# canSlaveV05_Abm.net
KiCad netlist of a schematic drawn in EAGLE
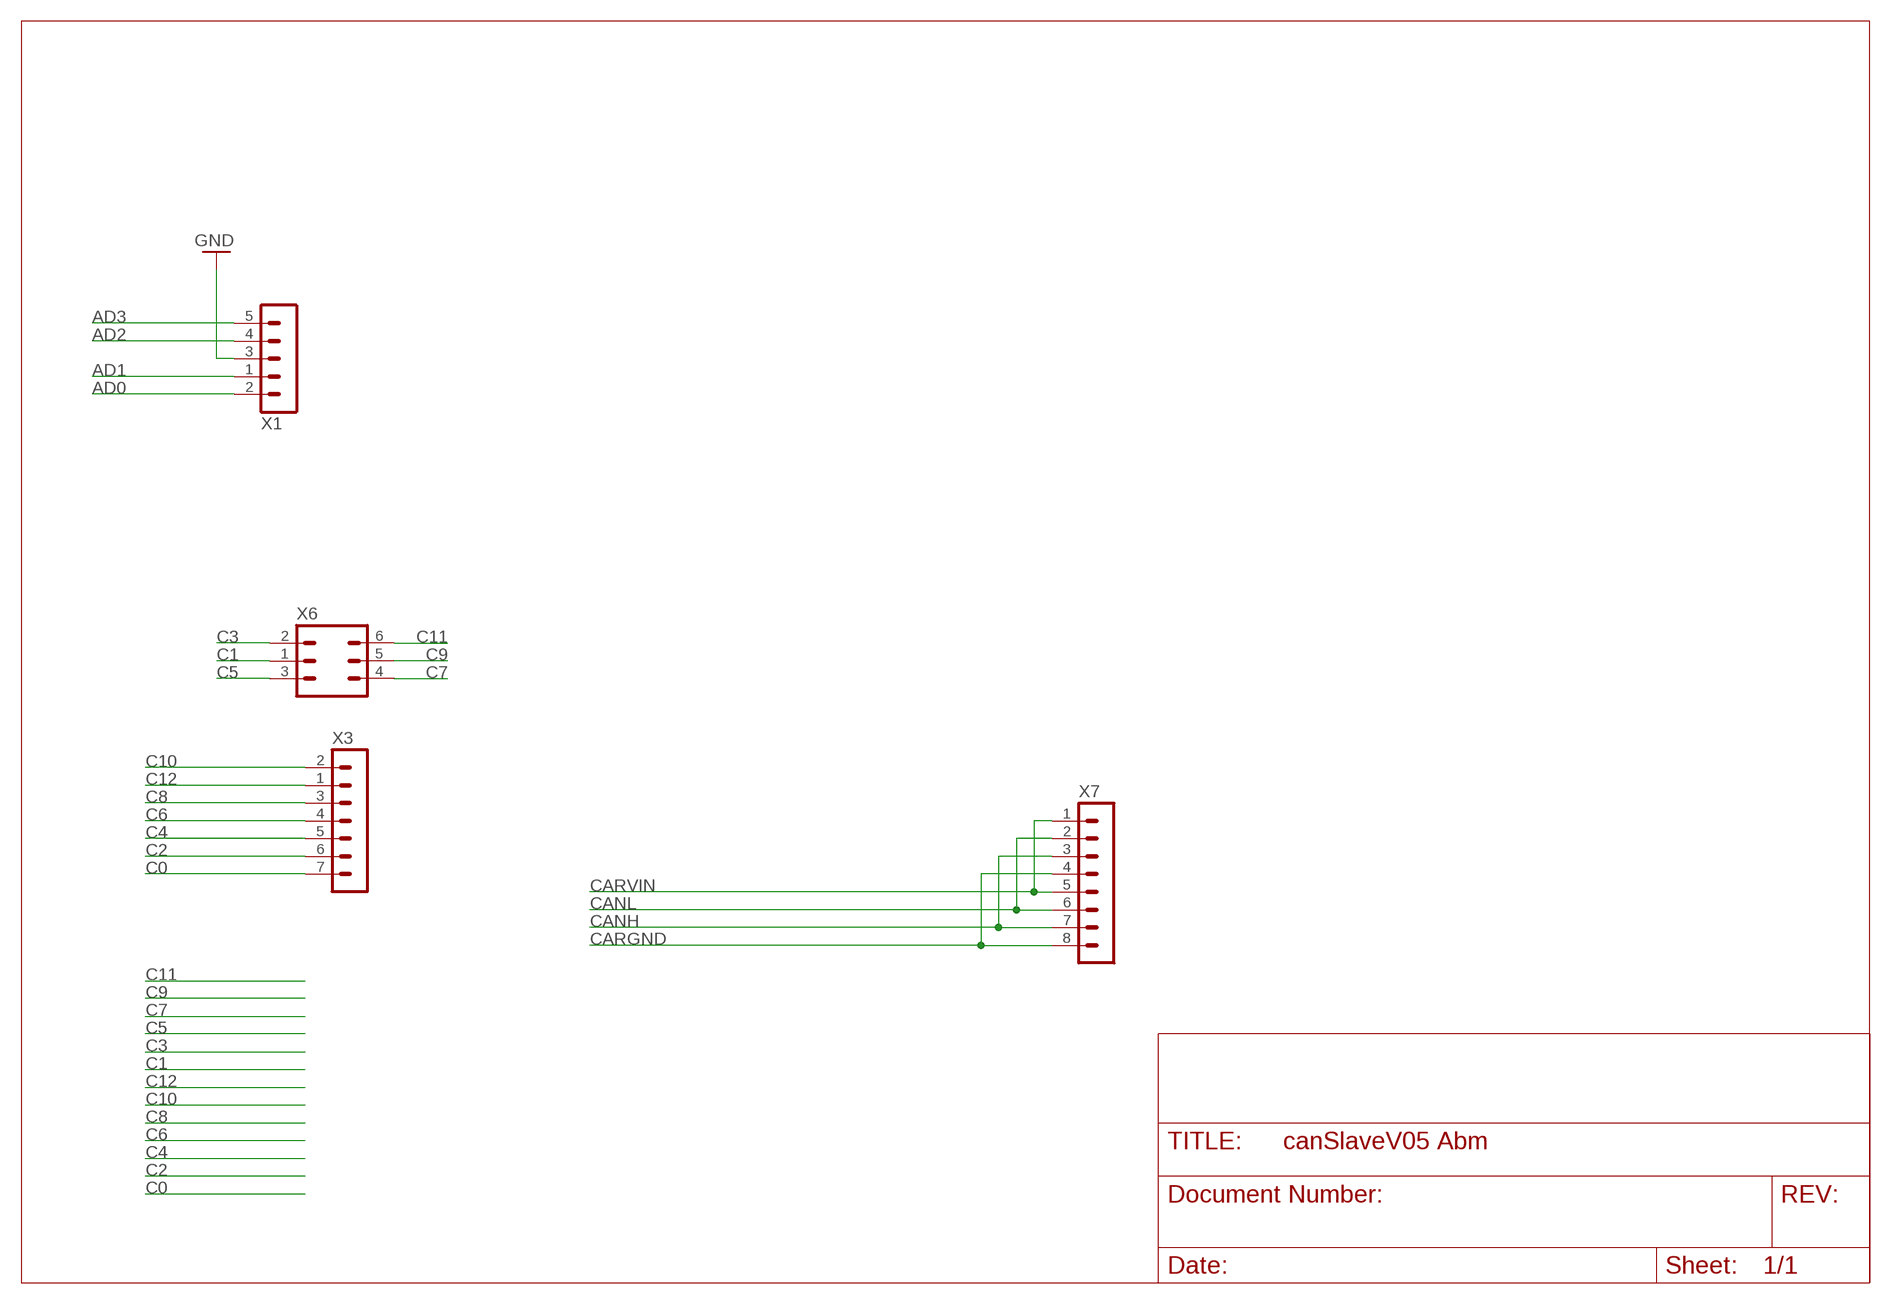
[diagram p0: schematic, sheet 1]

(export (version "E")
  (design (tool "Eeschema 10.0.6"))
  (components
    (comp (ref "X1")
      (value "HEADER_POS5_43650-0509")
      (footprint "eagle-import:43650-0509")
      (libsource (lib "eagle-import") (part "HEADER_POS5_?43650-0509"))
    )
    (comp (ref "X3")
      (value "HEADER_POS7_43650-0709")
      (footprint "eagle-import:43650-0709")
      (libsource (lib "eagle-import") (part "HEADER_POS7_?43650-0709"))
    )
    (comp (ref "X6")
      (value "HEADER_POS6_43650-0609")
      (footprint "eagle-import:43650-0609")
      (libsource (lib "eagle-import") (part "HEADER_POS6_?43650-0609"))
    )
    (comp (ref "X7")
      (value "HEADER_POS8_43045-0800")
      (footprint "eagle-import:43045-0800")
      (libsource (lib "eagle-import") (part "HEADER_POS8_?43045-0800"))
    )
  )
  (nets
    (net (code "1") (name "/AD0") (class "Default")
      (node (ref "X1") (pin "2") (pinfunction "1_2") (pintype "passive"))
    )
    (net (code "2") (name "/AD1") (class "Default")
      (node (ref "X1") (pin "1") (pinfunction "2_1") (pintype "passive"))
    )
    (net (code "3") (name "/AD2") (class "Default")
      (node (ref "X1") (pin "4") (pinfunction "4_4") (pintype "passive"))
    )
    (net (code "4") (name "/AD3") (class "Default")
      (node (ref "X1") (pin "5") (pinfunction "5_5") (pintype "passive"))
    )
    (net (code "5") (name "/C0") (class "Default")
      (node (ref "X3") (pin "7") (pinfunction "7_7") (pintype "passive"))
    )
    (net (code "6") (name "/C1") (class "Default")
      (node (ref "X6") (pin "1") (pinfunction "2_1") (pintype "passive"))
    )
    (net (code "7") (name "/C2") (class "Default")
      (node (ref "X3") (pin "6") (pinfunction "6_6") (pintype "passive"))
    )
    (net (code "8") (name "/C3") (class "Default")
      (node (ref "X6") (pin "2") (pinfunction "1_2") (pintype "passive"))
    )
    (net (code "9") (name "/C4") (class "Default")
      (node (ref "X3") (pin "5") (pinfunction "5_5") (pintype "passive"))
    )
    (net (code "10") (name "/C5") (class "Default")
      (node (ref "X6") (pin "3") (pinfunction "3_3") (pintype "passive"))
    )
    (net (code "11") (name "/C6") (class "Default")
      (node (ref "X3") (pin "4") (pinfunction "4_4") (pintype "passive"))
    )
    (net (code "12") (name "/C7") (class "Default")
      (node (ref "X6") (pin "4") (pinfunction "4_4") (pintype "passive"))
    )
    (net (code "13") (name "/C8") (class "Default")
      (node (ref "X3") (pin "3") (pinfunction "3_3") (pintype "passive"))
    )
    (net (code "14") (name "/C9") (class "Default")
      (node (ref "X6") (pin "5") (pinfunction "5_5") (pintype "passive"))
    )
    (net (code "15") (name "/C10") (class "Default")
      (node (ref "X3") (pin "2") (pinfunction "1_2") (pintype "passive"))
    )
    (net (code "16") (name "/C11") (class "Default")
      (node (ref "X6") (pin "6") (pinfunction "6_6") (pintype "passive"))
    )
    (net (code "17") (name "/C12") (class "Default")
      (node (ref "X3") (pin "1") (pinfunction "2_1") (pintype "passive"))
    )
    (net (code "18") (name "/CANH") (class "Default")
      (node (ref "X7") (pin "3") (pinfunction "3_3") (pintype "passive"))
      (node (ref "X7") (pin "7") (pinfunction "7_7") (pintype "passive"))
    )
    (net (code "19") (name "/CANL") (class "Default")
      (node (ref "X7") (pin "2") (pinfunction "2_2") (pintype "passive"))
      (node (ref "X7") (pin "6") (pinfunction "6_6") (pintype "passive"))
    )
    (net (code "20") (name "/CARGND") (class "Default")
      (node (ref "X7") (pin "4") (pinfunction "4_4") (pintype "passive"))
      (node (ref "X7") (pin "8") (pinfunction "8_8") (pintype "passive"))
    )
    (net (code "21") (name "/CARVIN") (class "Default")
      (node (ref "X7") (pin "1") (pinfunction "1_1") (pintype "passive"))
      (node (ref "X7") (pin "5") (pinfunction "5_5") (pintype "passive"))
    )
    (net (code "22") (name "GND") (class "Default")
      (node (ref "X1") (pin "3") (pinfunction "3_3") (pintype "passive"))
    )
  )
)
